# LCDbackpack.net
KiCad netlist of a schematic drawn in EAGLE
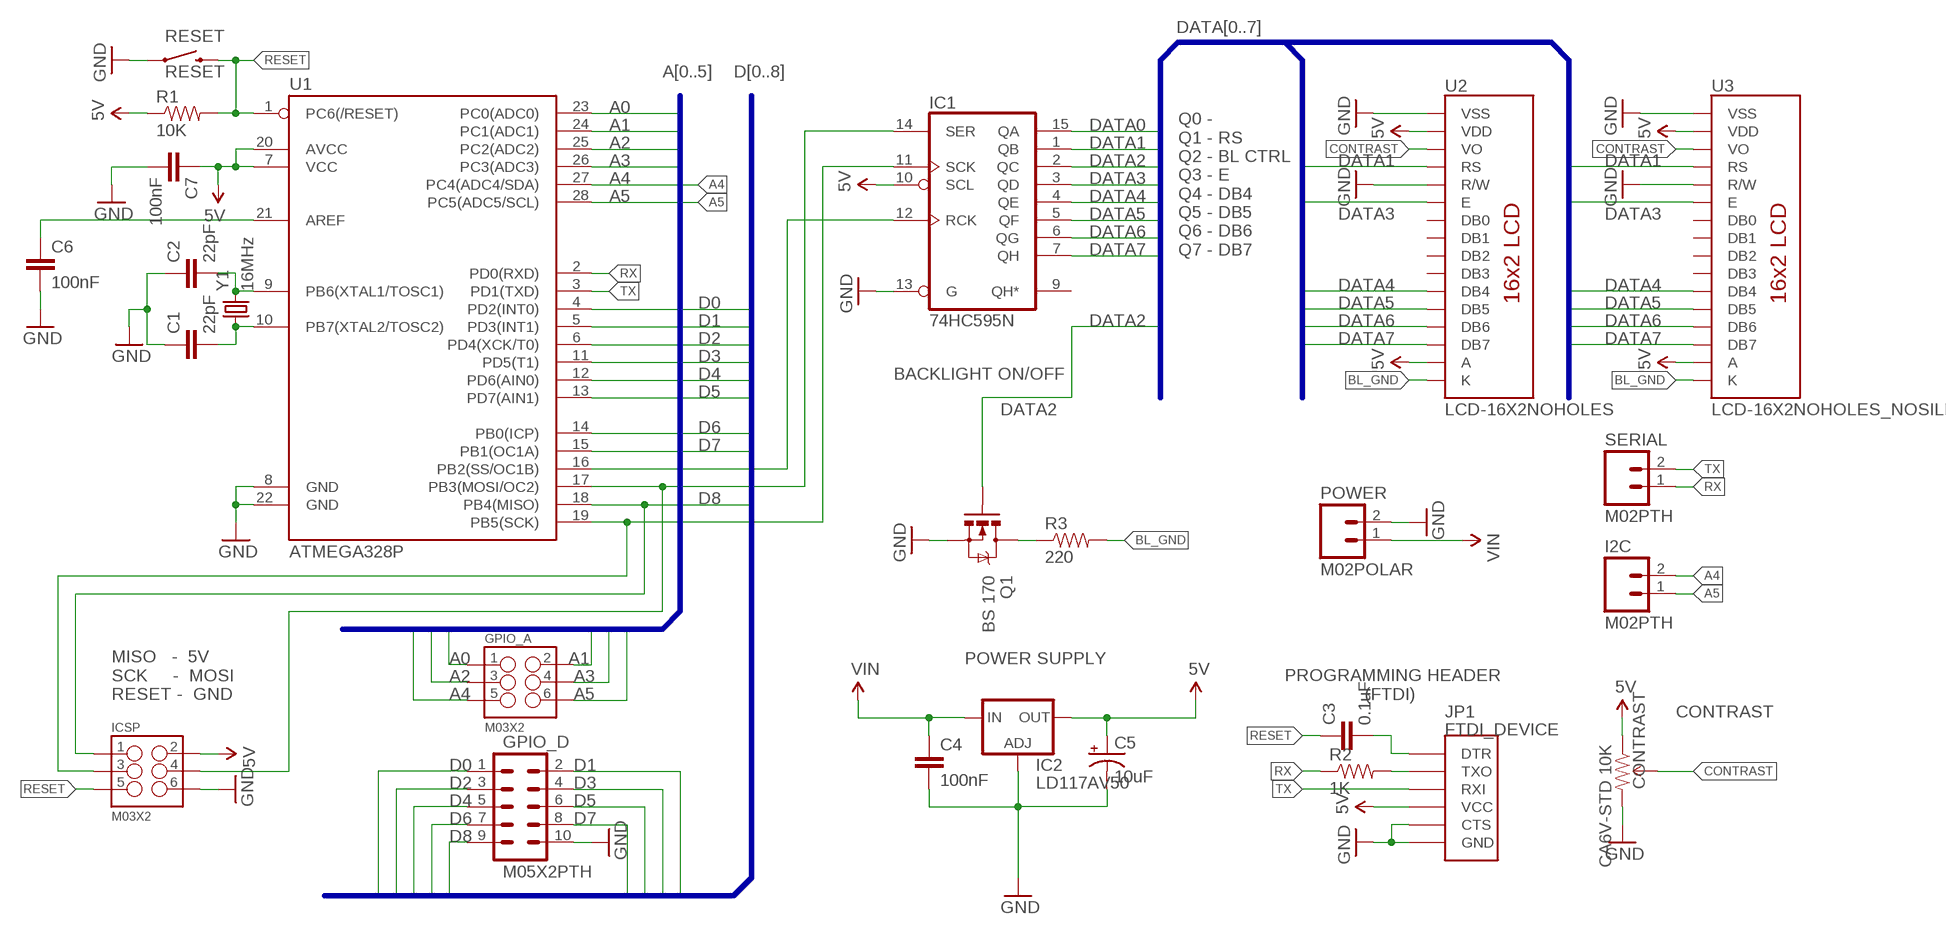
[diagram p0: schematic, sheet 1]

(export (version "E")
  (design (tool "Eeschema 10.0.6"))
  (components
    (comp (ref "C1")
      (value "22pF")
      (footprint "eagle-import:CAP-PTH-SMALL2")
      (libsource (lib "eagle-import") (part "CAPPTH2"))
    )
    (comp (ref "C2")
      (value "22pF")
      (footprint "eagle-import:CAP-PTH-SMALL2")
      (libsource (lib "eagle-import") (part "CAPPTH2"))
    )
    (comp (ref "C3")
      (value "0.1uF")
      (footprint "eagle-import:CAP-PTH-SMALL2")
      (libsource (lib "eagle-import") (part "CAPPTH2"))
    )
    (comp (ref "C4")
      (value "100nF")
      (footprint "eagle-import:CAP-PTH-SMALL2")
      (libsource (lib "eagle-import") (part "CAPPTH2"))
    )
    (comp (ref "C5")
      (value "10uF")
      (footprint "eagle-import:CPOL-RADIAL-10UF-25V")
      (libsource (lib "eagle-import") (part "CAP_POLPTH2"))
    )
    (comp (ref "C6")
      (value "100nF")
      (footprint "eagle-import:CAP-PTH-SMALL2")
      (libsource (lib "eagle-import") (part "CAPPTH2"))
    )
    (comp (ref "C7")
      (value "100nF")
      (footprint "eagle-import:CAP-PTH-SMALL2")
      (libsource (lib "eagle-import") (part "CAPPTH2"))
    )
    (comp (ref "CONTRAST")
      (value "CA6V-STD 10K")
      (footprint "eagle-import:TRIM_POT_PTH")
      (libsource (lib "eagle-import") (part "TRIMPOTPTH"))
    )
    (comp (ref "GPIO_A")
      (value "M03X2")
      (footprint "eagle-import:2X3")
      (libsource (lib "eagle-import") (part "M03X22X3_SILK_MALE_PTH"))
    )
    (comp (ref "GPIO_D")
      (value "M05X2PTH")
      (footprint "eagle-import:AVR_ICSP")
      (libsource (lib "eagle-import") (part "M05X2PTH"))
    )
    (comp (ref "I2C")
      (value "M02PTH")
      (footprint "eagle-import:1X02")
      (libsource (lib "eagle-import") (part "M02PTH"))
    )
    (comp (ref "IC1")
      (value "74HC595N")
      (footprint "eagle-import:DIL16")
      (libsource (lib "eagle-import") (part "74595NHC"))
    )
    (comp (ref "IC2")
      (value "LD117AV50")
      (footprint "eagle-import:TO220L1")
      (libsource (lib "eagle-import") (part "LD117A?V50"))
    )
    (comp (ref "ICSP")
      (value "M03X2")
      (footprint "eagle-import:2X3_POGO")
      (libsource (lib "eagle-import") (part "M03X2POGO_PINS"))
    )
    (comp (ref "JP1")
      (value "FTDI_DEVICE")
      (footprint "eagle-import:FTDI_DEVICE_SIDE")
      (libsource (lib "eagle-import") (part "FTDI_DEVICE"))
    )
    (comp (ref "POWER")
      (value "M02POLAR")
      (footprint "eagle-import:MOLEX-1X2")
      (libsource (lib "eagle-import") (part "M02POLAR"))
    )
    (comp (ref "Q1")
      (value "BS 170")
      (footprint "eagle-import:TO-92")
      (libsource (lib "eagle-import") (part "MOSFET-NCHANNEL2N7000"))
    )
    (comp (ref "R1")
      (value "10K")
      (footprint "eagle-import:AXIAL-0.3")
      (libsource (lib "eagle-import") (part "RESISTORAXIAL-0.3"))
    )
    (comp (ref "R2")
      (value "1K")
      (footprint "eagle-import:AXIAL-0.3")
      (libsource (lib "eagle-import") (part "RESISTORAXIAL-0.3"))
    )
    (comp (ref "R3")
      (value "220")
      (footprint "eagle-import:AXIAL-0.3")
      (libsource (lib "eagle-import") (part "RESISTORAXIAL-0.3"))
    )
    (comp (ref "RESET")
      (value "RESET")
      (footprint "eagle-import:TACTILE-PTH")
      (libsource (lib "eagle-import") (part "SWITCH-MOMENTARY-2PTH"))
    )
    (comp (ref "SERIAL")
      (value "M02PTH")
      (footprint "eagle-import:1X02")
      (libsource (lib "eagle-import") (part "M02PTH"))
    )
    (comp (ref "U1")
      (value "ATMEGA328P")
      (footprint "eagle-import:DIL28-3")
      (libsource (lib "eagle-import") (part "ATMEGA328P_PDIP"))
    )
    (comp (ref "U2")
      (value "LCD-16X2NOHOLES")
      (footprint "eagle-import:LCD-16X2_NOHOLES")
      (libsource (lib "eagle-import") (part "LCD-16X2NOHOLES"))
    )
    (comp (ref "U3")
      (value "LCD-16X2NOHOLES_NOSILK")
      (footprint "eagle-import:LCD-8X2_NOHOLES_NOSILK")
      (libsource (lib "eagle-import") (part "LCD-16X2NOHOLES_NOSILK"))
    )
    (comp (ref "Y1")
      (value "16MHz")
      (footprint "eagle-import:HC49US")
      (libsource (lib "eagle-import") (part "CRYSTALHC49US"))
    )
  )
  (nets
    (net (code "1") (name "/A0") (class "Default")
      (node (ref "GPIO_A") (pin "1") (pinfunction "1_1") (pintype "bidirectional"))
      (node (ref "U1") (pin "23") (pinfunction "PC0(ADC0)_23") (pintype "bidirectional"))
    )
    (net (code "2") (name "/A1") (class "Default")
      (node (ref "GPIO_A") (pin "2") (pinfunction "2_2") (pintype "bidirectional"))
      (node (ref "U1") (pin "24") (pinfunction "PC1(ADC1)_24") (pintype "bidirectional"))
    )
    (net (code "3") (name "/A2") (class "Default")
      (node (ref "GPIO_A") (pin "3") (pinfunction "3_3") (pintype "bidirectional"))
      (node (ref "U1") (pin "25") (pinfunction "PC2(ADC2)_25") (pintype "bidirectional"))
    )
    (net (code "4") (name "/A3") (class "Default")
      (node (ref "GPIO_A") (pin "4") (pinfunction "4_4") (pintype "bidirectional"))
      (node (ref "U1") (pin "26") (pinfunction "PC3(ADC3)_26") (pintype "bidirectional"))
    )
    (net (code "6") (name "/D0") (class "Default")
      (node (ref "GPIO_D") (pin "1") (pinfunction "1_1") (pintype "passive"))
      (node (ref "U1") (pin "4") (pinfunction "PD2(INT0)_4") (pintype "bidirectional"))
    )
    (net (code "7") (name "/D1") (class "Default")
      (node (ref "GPIO_D") (pin "2") (pinfunction "2_2") (pintype "passive"))
      (node (ref "U1") (pin "5") (pinfunction "PD3(INT1)_5") (pintype "bidirectional"))
    )
    (net (code "8") (name "/D2") (class "Default")
      (node (ref "GPIO_D") (pin "3") (pinfunction "3_3") (pintype "passive"))
      (node (ref "U1") (pin "6") (pinfunction "PD4(XCK/T0)_6") (pintype "bidirectional"))
    )
    (net (code "9") (name "/D3") (class "Default")
      (node (ref "GPIO_D") (pin "4") (pinfunction "4_4") (pintype "passive"))
      (node (ref "U1") (pin "11") (pinfunction "PD5(T1)_11") (pintype "bidirectional"))
    )
    (net (code "10") (name "/D4") (class "Default")
      (node (ref "GPIO_D") (pin "5") (pinfunction "5_5") (pintype "passive"))
      (node (ref "U1") (pin "12") (pinfunction "PD6(AIN0)_12") (pintype "bidirectional"))
    )
    (net (code "11") (name "/D5") (class "Default")
      (node (ref "GPIO_D") (pin "6") (pinfunction "6_6") (pintype "passive"))
      (node (ref "U1") (pin "13") (pinfunction "PD7(AIN1)_13") (pintype "bidirectional"))
    )
    (net (code "12") (name "/D6") (class "Default")
      (node (ref "GPIO_D") (pin "7") (pinfunction "7_7") (pintype "passive"))
      (node (ref "U1") (pin "14") (pinfunction "PB0(ICP)_14") (pintype "bidirectional"))
    )
    (net (code "13") (name "/D7") (class "Default")
      (node (ref "GPIO_D") (pin "8") (pinfunction "8_8") (pintype "passive"))
      (node (ref "U1") (pin "15") (pinfunction "PB1(OC1A)_15") (pintype "bidirectional"))
    )
    (net (code "14") (name "/D8") (class "Default")
      (node (ref "GPIO_D") (pin "9") (pinfunction "9_9") (pintype "passive"))
      (node (ref "ICSP") (pin "P$1") (pinfunction "1_P$1") (pintype "bidirectional"))
      (node (ref "U1") (pin "18") (pinfunction "PB4(MISO)_18") (pintype "bidirectional"))
    )
    (net (code "15") (name "/DATA0") (class "Default")
      (node (ref "IC1") (pin "15") (pinfunction "QA_15") (pintype "tri_state"))
    )
    (net (code "16") (name "/DATA1") (class "Default")
      (node (ref "IC1") (pin "1") (pinfunction "QB_1") (pintype "tri_state"))
      (node (ref "U2") (pin "4") (pinfunction "RS_4") (pintype "input"))
      (node (ref "U3") (pin "4") (pinfunction "RS_4") (pintype "input"))
    )
    (net (code "17") (name "/DATA2") (class "Default")
      (node (ref "IC1") (pin "2") (pinfunction "QC_2") (pintype "tri_state"))
      (node (ref "Q1") (pin "2") (pinfunction "G_2") (pintype "passive"))
    )
    (net (code "18") (name "/DATA3") (class "Default")
      (node (ref "IC1") (pin "3") (pinfunction "QD_3") (pintype "tri_state"))
      (node (ref "U2") (pin "6") (pinfunction "E_6") (pintype "input"))
      (node (ref "U3") (pin "6") (pinfunction "E_6") (pintype "input"))
    )
    (net (code "19") (name "/DATA4") (class "Default")
      (node (ref "IC1") (pin "4") (pinfunction "QE_4") (pintype "tri_state"))
      (node (ref "U2") (pin "11") (pinfunction "DB4_11") (pintype "bidirectional"))
      (node (ref "U3") (pin "11") (pinfunction "DB4_11") (pintype "bidirectional"))
    )
    (net (code "20") (name "/DATA5") (class "Default")
      (node (ref "IC1") (pin "5") (pinfunction "QF_5") (pintype "tri_state"))
      (node (ref "U2") (pin "12") (pinfunction "DB5_12") (pintype "bidirectional"))
      (node (ref "U3") (pin "12") (pinfunction "DB5_12") (pintype "bidirectional"))
    )
    (net (code "21") (name "/DATA6") (class "Default")
      (node (ref "IC1") (pin "6") (pinfunction "QG_6") (pintype "tri_state"))
      (node (ref "U2") (pin "13") (pinfunction "DB6_13") (pintype "bidirectional"))
      (node (ref "U3") (pin "13") (pinfunction "DB6_13") (pintype "bidirectional"))
    )
    (net (code "22") (name "/DATA7") (class "Default")
      (node (ref "IC1") (pin "7") (pinfunction "QH_7") (pintype "tri_state"))
      (node (ref "U2") (pin "14") (pinfunction "DB7_14") (pintype "bidirectional"))
      (node (ref "U3") (pin "14") (pinfunction "DB7_14") (pintype "bidirectional"))
    )
    (net (code "25") (name "5V") (class "Default")
      (node (ref "C5") (pin "1") (pinfunction "+_1") (pintype "passive"))
      (node (ref "C7") (pin "1") (pinfunction "1_1") (pintype "passive"))
      (node (ref "CONTRAST") (pin "1") (pinfunction "CCW_1") (pintype "passive"))
      (node (ref "IC1") (pin "10") (pinfunction "SCL_10") (pintype "input"))
      (node (ref "IC2") (pin "2") (pinfunction "OUT_2") (pintype "passive"))
      (node (ref "ICSP") (pin "P$2") (pinfunction "2_P$2") (pintype "bidirectional"))
      (node (ref "JP1") (pin "P$4") (pinfunction "VCC_P$4") (pintype "bidirectional"))
      (node (ref "R1") (pin "P$1") (pinfunction "1_P$1") (pintype "passive"))
      (node (ref "U1") (pin "20") (pinfunction "AVCC_20") (pintype "bidirectional"))
      (node (ref "U1") (pin "7") (pinfunction "VCC_7") (pintype "bidirectional"))
      (node (ref "U2") (pin "15") (pinfunction "A_15") (pintype "power_in"))
      (node (ref "U2") (pin "2") (pinfunction "VDD_2") (pintype "power_in"))
      (node (ref "U3") (pin "15") (pinfunction "A_15") (pintype "power_in"))
      (node (ref "U3") (pin "2") (pinfunction "VDD_2") (pintype "power_in"))
    )
    (net (code "26") (name "A4") (class "Default")
      (node (ref "GPIO_A") (pin "5") (pinfunction "5_5") (pintype "bidirectional"))
      (node (ref "I2C") (pin "2") (pinfunction "2_2") (pintype "passive"))
      (node (ref "U1") (pin "27") (pinfunction "PC4(ADC4/SDA)_27") (pintype "bidirectional"))
    )
    (net (code "27") (name "A5") (class "Default")
      (node (ref "GPIO_A") (pin "6") (pinfunction "6_6") (pintype "bidirectional"))
      (node (ref "I2C") (pin "1") (pinfunction "1_1") (pintype "passive"))
      (node (ref "U1") (pin "28") (pinfunction "PC5(ADC5/SCL)_28") (pintype "bidirectional"))
    )
    (net (code "28") (name "BL_GND") (class "Default")
      (node (ref "R3") (pin "P$2") (pinfunction "2_P$2") (pintype "passive"))
      (node (ref "U2") (pin "16") (pinfunction "K_16") (pintype "power_in"))
      (node (ref "U3") (pin "16") (pinfunction "K_16") (pintype "power_in"))
    )
    (net (code "29") (name "CONTRAST") (class "Default")
      (node (ref "CONTRAST") (pin "2") (pinfunction "WIPER_2") (pintype "passive"))
      (node (ref "U2") (pin "3") (pinfunction "VO_3") (pintype "bidirectional"))
      (node (ref "U3") (pin "3") (pinfunction "VO_3") (pintype "bidirectional"))
    )
    (net (code "30") (name "GND") (class "Default")
      (node (ref "C1") (pin "1") (pinfunction "1_1") (pintype "passive"))
      (node (ref "C2") (pin "1") (pinfunction "1_1") (pintype "passive"))
      (node (ref "C4") (pin "2") (pinfunction "2_2") (pintype "passive"))
      (node (ref "C5") (pin "2") (pinfunction "-_2") (pintype "passive"))
      (node (ref "C6") (pin "2") (pinfunction "2_2") (pintype "passive"))
      (node (ref "C7") (pin "2") (pinfunction "2_2") (pintype "passive"))
      (node (ref "CONTRAST") (pin "3") (pinfunction "CW_3") (pintype "passive"))
      (node (ref "GPIO_D") (pin "10") (pinfunction "10_10") (pintype "passive"))
      (node (ref "IC1") (pin "13") (pinfunction "G_13") (pintype "input"))
      (node (ref "IC2") (pin "1") (pinfunction "ADJ_1") (pintype "input"))
      (node (ref "ICSP") (pin "P$6") (pinfunction "6_P$6") (pintype "bidirectional"))
      (node (ref "JP1") (pin "P$5") (pinfunction "CTS_P$5") (pintype "bidirectional"))
      (node (ref "JP1") (pin "P$6") (pinfunction "GND_P$6") (pintype "bidirectional"))
      (node (ref "POWER") (pin "2") (pinfunction "2_2") (pintype "passive"))
      (node (ref "Q1") (pin "1") (pinfunction "S_1") (pintype "passive"))
      (node (ref "RESET") (pin "1") (pinfunction "1_1") (pintype "passive"))
      (node (ref "U1") (pin "22") (pinfunction "GND_22") (pintype "bidirectional"))
      (node (ref "U1") (pin "8") (pinfunction "GND_8") (pintype "bidirectional"))
      (node (ref "U2") (pin "1") (pinfunction "VSS_1") (pintype "power_in"))
      (node (ref "U2") (pin "5") (pinfunction "R/W_5") (pintype "input"))
      (node (ref "U3") (pin "1") (pinfunction "VSS_1") (pintype "power_in"))
      (node (ref "U3") (pin "5") (pinfunction "R/W_5") (pintype "input"))
    )
    (net (code "31") (name "Net-(IC1A-RCK)") (class "Default")
      (node (ref "IC1") (pin "12") (pinfunction "RCK_12") (pintype "input"))
      (node (ref "U1") (pin "16") (pinfunction "PB2(SS/OC1B)_16") (pintype "bidirectional"))
    )
    (net (code "32") (name "Net-(IC1A-SCK)") (class "Default")
      (node (ref "IC1") (pin "11") (pinfunction "SCK_11") (pintype "input"))
      (node (ref "ICSP") (pin "P$3") (pinfunction "3_P$3") (pintype "bidirectional"))
      (node (ref "U1") (pin "19") (pinfunction "PB5(SCK)_19") (pintype "bidirectional"))
    )
    (net (code "33") (name "Net-(IC1A-SER)") (class "Default")
      (node (ref "IC1") (pin "14") (pinfunction "SER_14") (pintype "input"))
      (node (ref "ICSP") (pin "P$4") (pinfunction "4_P$4") (pintype "bidirectional"))
      (node (ref "U1") (pin "17") (pinfunction "PB3(MOSI/OC2)_17") (pintype "bidirectional"))
    )
    (net (code "34") (name "Net-(JP1-DTR)") (class "Default")
      (node (ref "C3") (pin "2") (pinfunction "2_2") (pintype "passive"))
      (node (ref "JP1") (pin "P$1") (pinfunction "DTR_P$1") (pintype "bidirectional"))
    )
    (net (code "35") (name "Net-(JP1-TXO)") (class "Default")
      (node (ref "JP1") (pin "P$2") (pinfunction "TXO_P$2") (pintype "bidirectional"))
      (node (ref "R2") (pin "P$2") (pinfunction "2_P$2") (pintype "passive"))
    )
    (net (code "36") (name "Net-(Q1-D)") (class "Default")
      (node (ref "Q1") (pin "3") (pinfunction "D_3") (pintype "passive"))
      (node (ref "R3") (pin "P$1") (pinfunction "1_P$1") (pintype "passive"))
    )
    (net (code "37") (name "Net-(U1-AREF)") (class "Default")
      (node (ref "C6") (pin "1") (pinfunction "1_1") (pintype "passive"))
      (node (ref "U1") (pin "21") (pinfunction "AREF_21") (pintype "bidirectional"))
    )
    (net (code "38") (name "Net-(U1-PB6(XTAL1{slash}TOSC1))") (class "Default")
      (node (ref "C2") (pin "2") (pinfunction "2_2") (pintype "passive"))
      (node (ref "U1") (pin "9") (pinfunction "PB6(XTAL1/TOSC1)_9") (pintype "bidirectional"))
      (node (ref "Y1") (pin "2") (pinfunction "2_2") (pintype "passive"))
    )
    (net (code "39") (name "Net-(U1-PB7(XTAL2{slash}TOSC2))") (class "Default")
      (node (ref "C1") (pin "2") (pinfunction "2_2") (pintype "passive"))
      (node (ref "U1") (pin "10") (pinfunction "PB7(XTAL2/TOSC2)_10") (pintype "bidirectional"))
      (node (ref "Y1") (pin "1") (pinfunction "1_1") (pintype "passive"))
    )
    (net (code "40") (name "RESET") (class "Default")
      (node (ref "C3") (pin "1") (pinfunction "1_1") (pintype "passive"))
      (node (ref "ICSP") (pin "P$5") (pinfunction "5_P$5") (pintype "bidirectional"))
      (node (ref "R1") (pin "P$2") (pinfunction "2_P$2") (pintype "passive"))
      (node (ref "RESET") (pin "3") (pinfunction "2_3") (pintype "passive"))
      (node (ref "U1") (pin "1") (pinfunction "PC6(/RESET)_1") (pintype "bidirectional"))
    )
    (net (code "41") (name "RX") (class "Default")
      (node (ref "R2") (pin "P$1") (pinfunction "1_P$1") (pintype "passive"))
      (node (ref "SERIAL") (pin "1") (pinfunction "1_1") (pintype "passive"))
      (node (ref "U1") (pin "2") (pinfunction "PD0(RXD)_2") (pintype "bidirectional"))
    )
    (net (code "42") (name "TX") (class "Default")
      (node (ref "JP1") (pin "P$3") (pinfunction "RXI_P$3") (pintype "bidirectional"))
      (node (ref "SERIAL") (pin "2") (pinfunction "2_2") (pintype "passive"))
      (node (ref "U1") (pin "3") (pinfunction "PD1(TXD)_3") (pintype "bidirectional"))
    )
    (net (code "43") (name "VIN") (class "Default")
      (node (ref "C4") (pin "1") (pinfunction "1_1") (pintype "passive"))
      (node (ref "IC2") (pin "3") (pinfunction "IN_3") (pintype "input"))
      (node (ref "POWER") (pin "1") (pinfunction "1_1") (pintype "passive"))
    )
    (net (code "44") (name "unconnected-(IC1A-QH*-Pad9)") (class "Default")
      (node (ref "IC1") (pin "9") (pinfunction "QH*_9") (pintype "tri_state"))
    )
    (net (code "45") (name "unconnected-(U2-DB0-Pad7)") (class "Default")
      (node (ref "U2") (pin "7") (pinfunction "DB0_7") (pintype "bidirectional"))
    )
    (net (code "46") (name "unconnected-(U2-DB1-Pad8)") (class "Default")
      (node (ref "U2") (pin "8") (pinfunction "DB1_8") (pintype "bidirectional"))
    )
    (net (code "47") (name "unconnected-(U2-DB2-Pad9)") (class "Default")
      (node (ref "U2") (pin "9") (pinfunction "DB2_9") (pintype "bidirectional"))
    )
    (net (code "48") (name "unconnected-(U2-DB3-Pad10)") (class "Default")
      (node (ref "U2") (pin "10") (pinfunction "DB3_10") (pintype "bidirectional"))
    )
    (net (code "49") (name "unconnected-(U3-DB0-Pad7)") (class "Default")
      (node (ref "U3") (pin "7") (pinfunction "DB0_7") (pintype "bidirectional"))
    )
    (net (code "50") (name "unconnected-(U3-DB1-Pad8)") (class "Default")
      (node (ref "U3") (pin "8") (pinfunction "DB1_8") (pintype "bidirectional"))
    )
    (net (code "51") (name "unconnected-(U3-DB2-Pad9)") (class "Default")
      (node (ref "U3") (pin "9") (pinfunction "DB2_9") (pintype "bidirectional"))
    )
    (net (code "52") (name "unconnected-(U3-DB3-Pad10)") (class "Default")
      (node (ref "U3") (pin "10") (pinfunction "DB3_10") (pintype "bidirectional"))
    )
  )
)
